# Sheet_1.net
KiCad netlist of a schematic drawn in EasyEDA
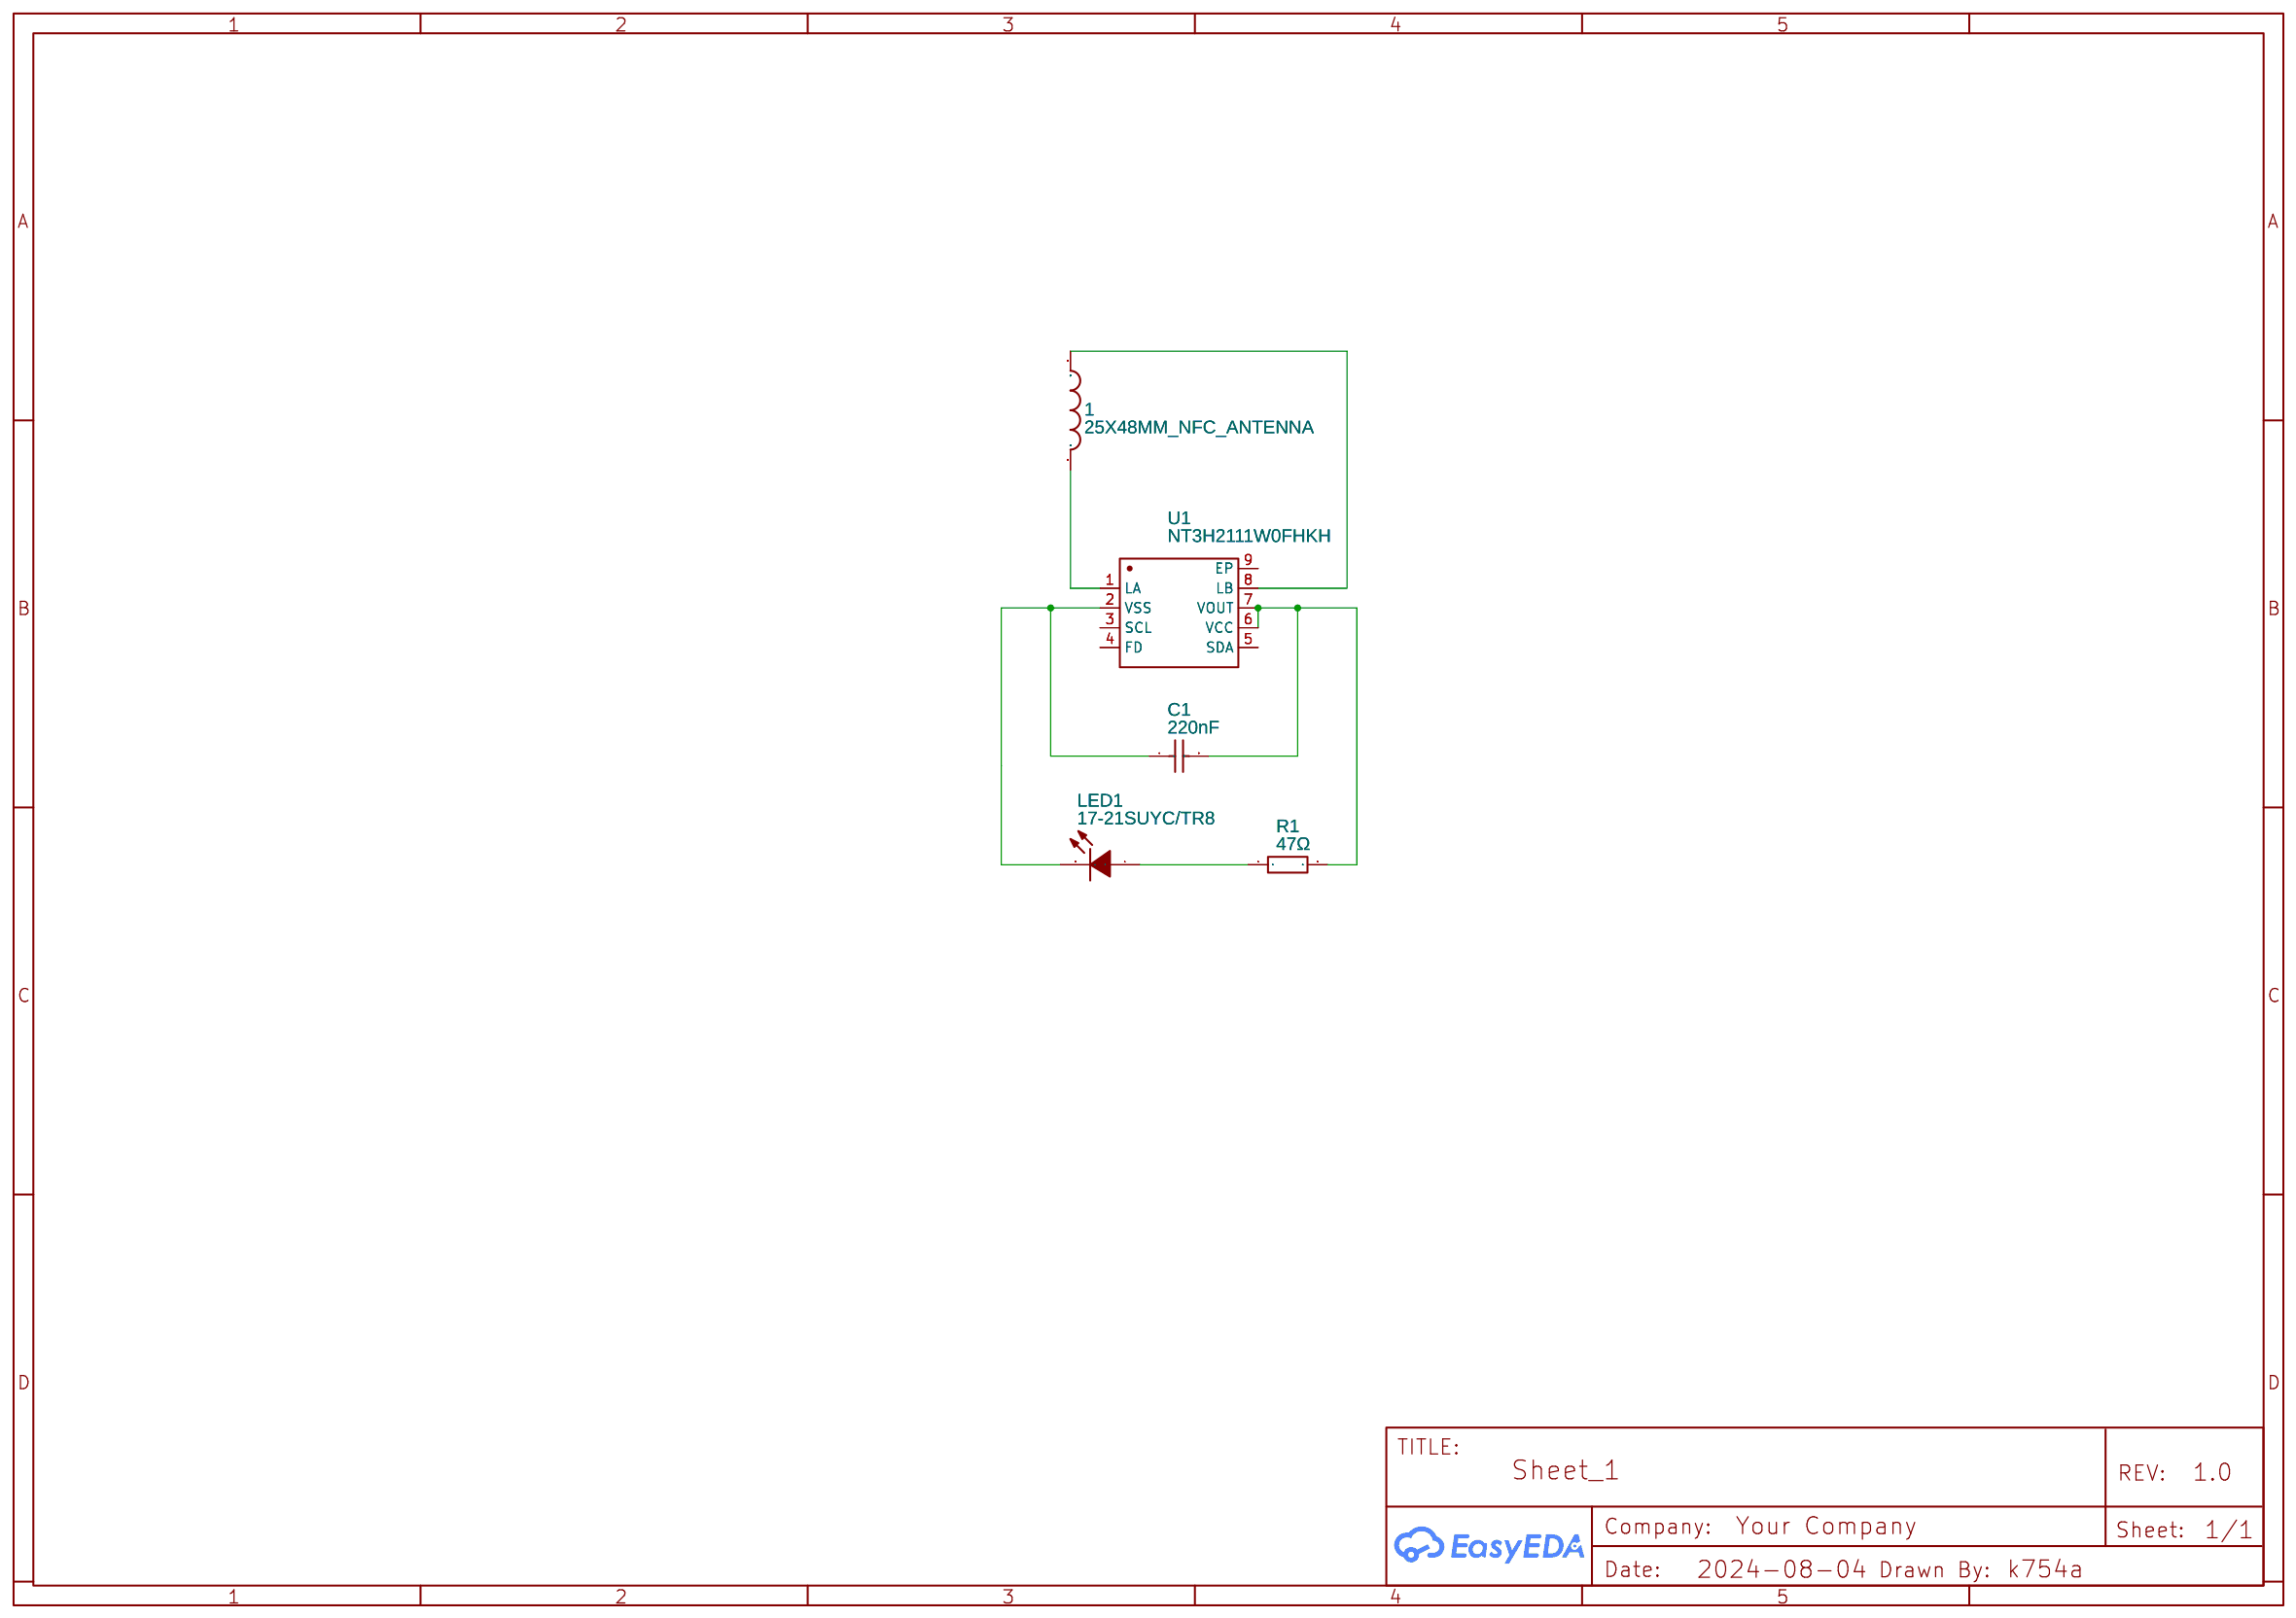
[diagram p0: schematic sheet]

(export (version "E")
  (design (tool "Eeschema 10.0.6"))
  (components
    (comp (ref "1") (value "25X48MM_NFC_ANTENNA") (libsource (lib "") (part "25X48MM_NFC_ANTENNA")))
    (comp (ref "C1")
      (value "220nF")
      (fields
        (field (name "Manufacturer Part") "CL10B224KA8NNNC")
        (field (name "Manufacturer") "SAMSUNG(三星)")
      )
      (libsource (lib "") (part "CL10B224KA8NNNC"))
    )
    (comp (ref "LED1")
      (value "17-21SUYC/TR8")
      (fields (field (name "Manufacturer Part") "KT-0805黄灯") (field (name "Manufacturer") "KENTO"))
      (libsource (lib "") (part "17-21SUYC/TR8"))
    )
    (comp (ref "R1")
      (value "47Ω")
      (fields
        (field (name "Manufacturer Part") "0603WAF470JT5E")
        (field (name "Manufacturer") "UNI-ROYAL(厚声)")
      )
      (libsource (lib "") (part "0603WAF470JT5E"))
    )
    (comp (ref "U1")
      (value "NT3H2111W0FHKH")
      (fields (field (name "Manufacturer") "NXP(恩智浦)"))
      (libsource (lib "") (part "NT3H2111W0FHKH"))
    )
  )
  (nets
    (net (code "1") (name "Net-(LED1-+)") (class "Default")
      (node (ref "LED1") (pin "1") (pinfunction "+_1") (pintype "unspecified"))
      (node (ref "R1") (pin "1") (pinfunction "1_1") (pintype "input"))
    )
    (net (code "2") (name "Net-(LED1--)") (class "Default")
      (node (ref "C1") (pin "1") (pinfunction "1_1") (pintype "input"))
      (node (ref "LED1") (pin "2") (pinfunction "-_2") (pintype "unspecified"))
      (node (ref "U1") (pin "2") (pinfunction "VSS_2") (pintype "unspecified"))
    )
    (net (code "3") (name "Net-(U1-LA)") (class "Default")
      (node (ref "1") (pin "P$2") (pinfunction "P$2_P$2") (pintype "bidirectional"))
      (node (ref "U1") (pin "1") (pinfunction "LA_1") (pintype "unspecified"))
    )
    (net (code "4") (name "Net-(U1-LB)") (class "Default")
      (node (ref "1") (pin "P$1") (pinfunction "P$1_P$1") (pintype "bidirectional"))
      (node (ref "U1") (pin "8") (pinfunction "LB_8") (pintype "unspecified"))
    )
    (net (code "5") (name "Net-(U1-VCC)") (class "Default")
      (node (ref "C1") (pin "2") (pinfunction "2_2") (pintype "input"))
      (node (ref "R1") (pin "2") (pinfunction "2_2") (pintype "input"))
      (node (ref "U1") (pin "6") (pinfunction "VCC_6") (pintype "unspecified"))
      (node (ref "U1") (pin "7") (pinfunction "VOUT_7") (pintype "unspecified"))
    )
    (net (code "6") (name "unconnected-(U1-EP-Pad9)") (class "Default")
      (node (ref "U1") (pin "9") (pinfunction "EP_9") (pintype "unspecified"))
    )
    (net (code "7") (name "unconnected-(U1-FD-Pad4)") (class "Default")
      (node (ref "U1") (pin "4") (pinfunction "FD_4") (pintype "unspecified"))
    )
    (net (code "8") (name "unconnected-(U1-SCL-Pad3)") (class "Default")
      (node (ref "U1") (pin "3") (pinfunction "SCL_3") (pintype "unspecified"))
    )
    (net (code "9") (name "unconnected-(U1-SDA-Pad5)") (class "Default")
      (node (ref "U1") (pin "5") (pinfunction "SDA_5") (pintype "unspecified"))
    )
  )
)
